# ETH_PCIE_PHY.net
KiCad netlist of a schematic drawn in Altium Designer
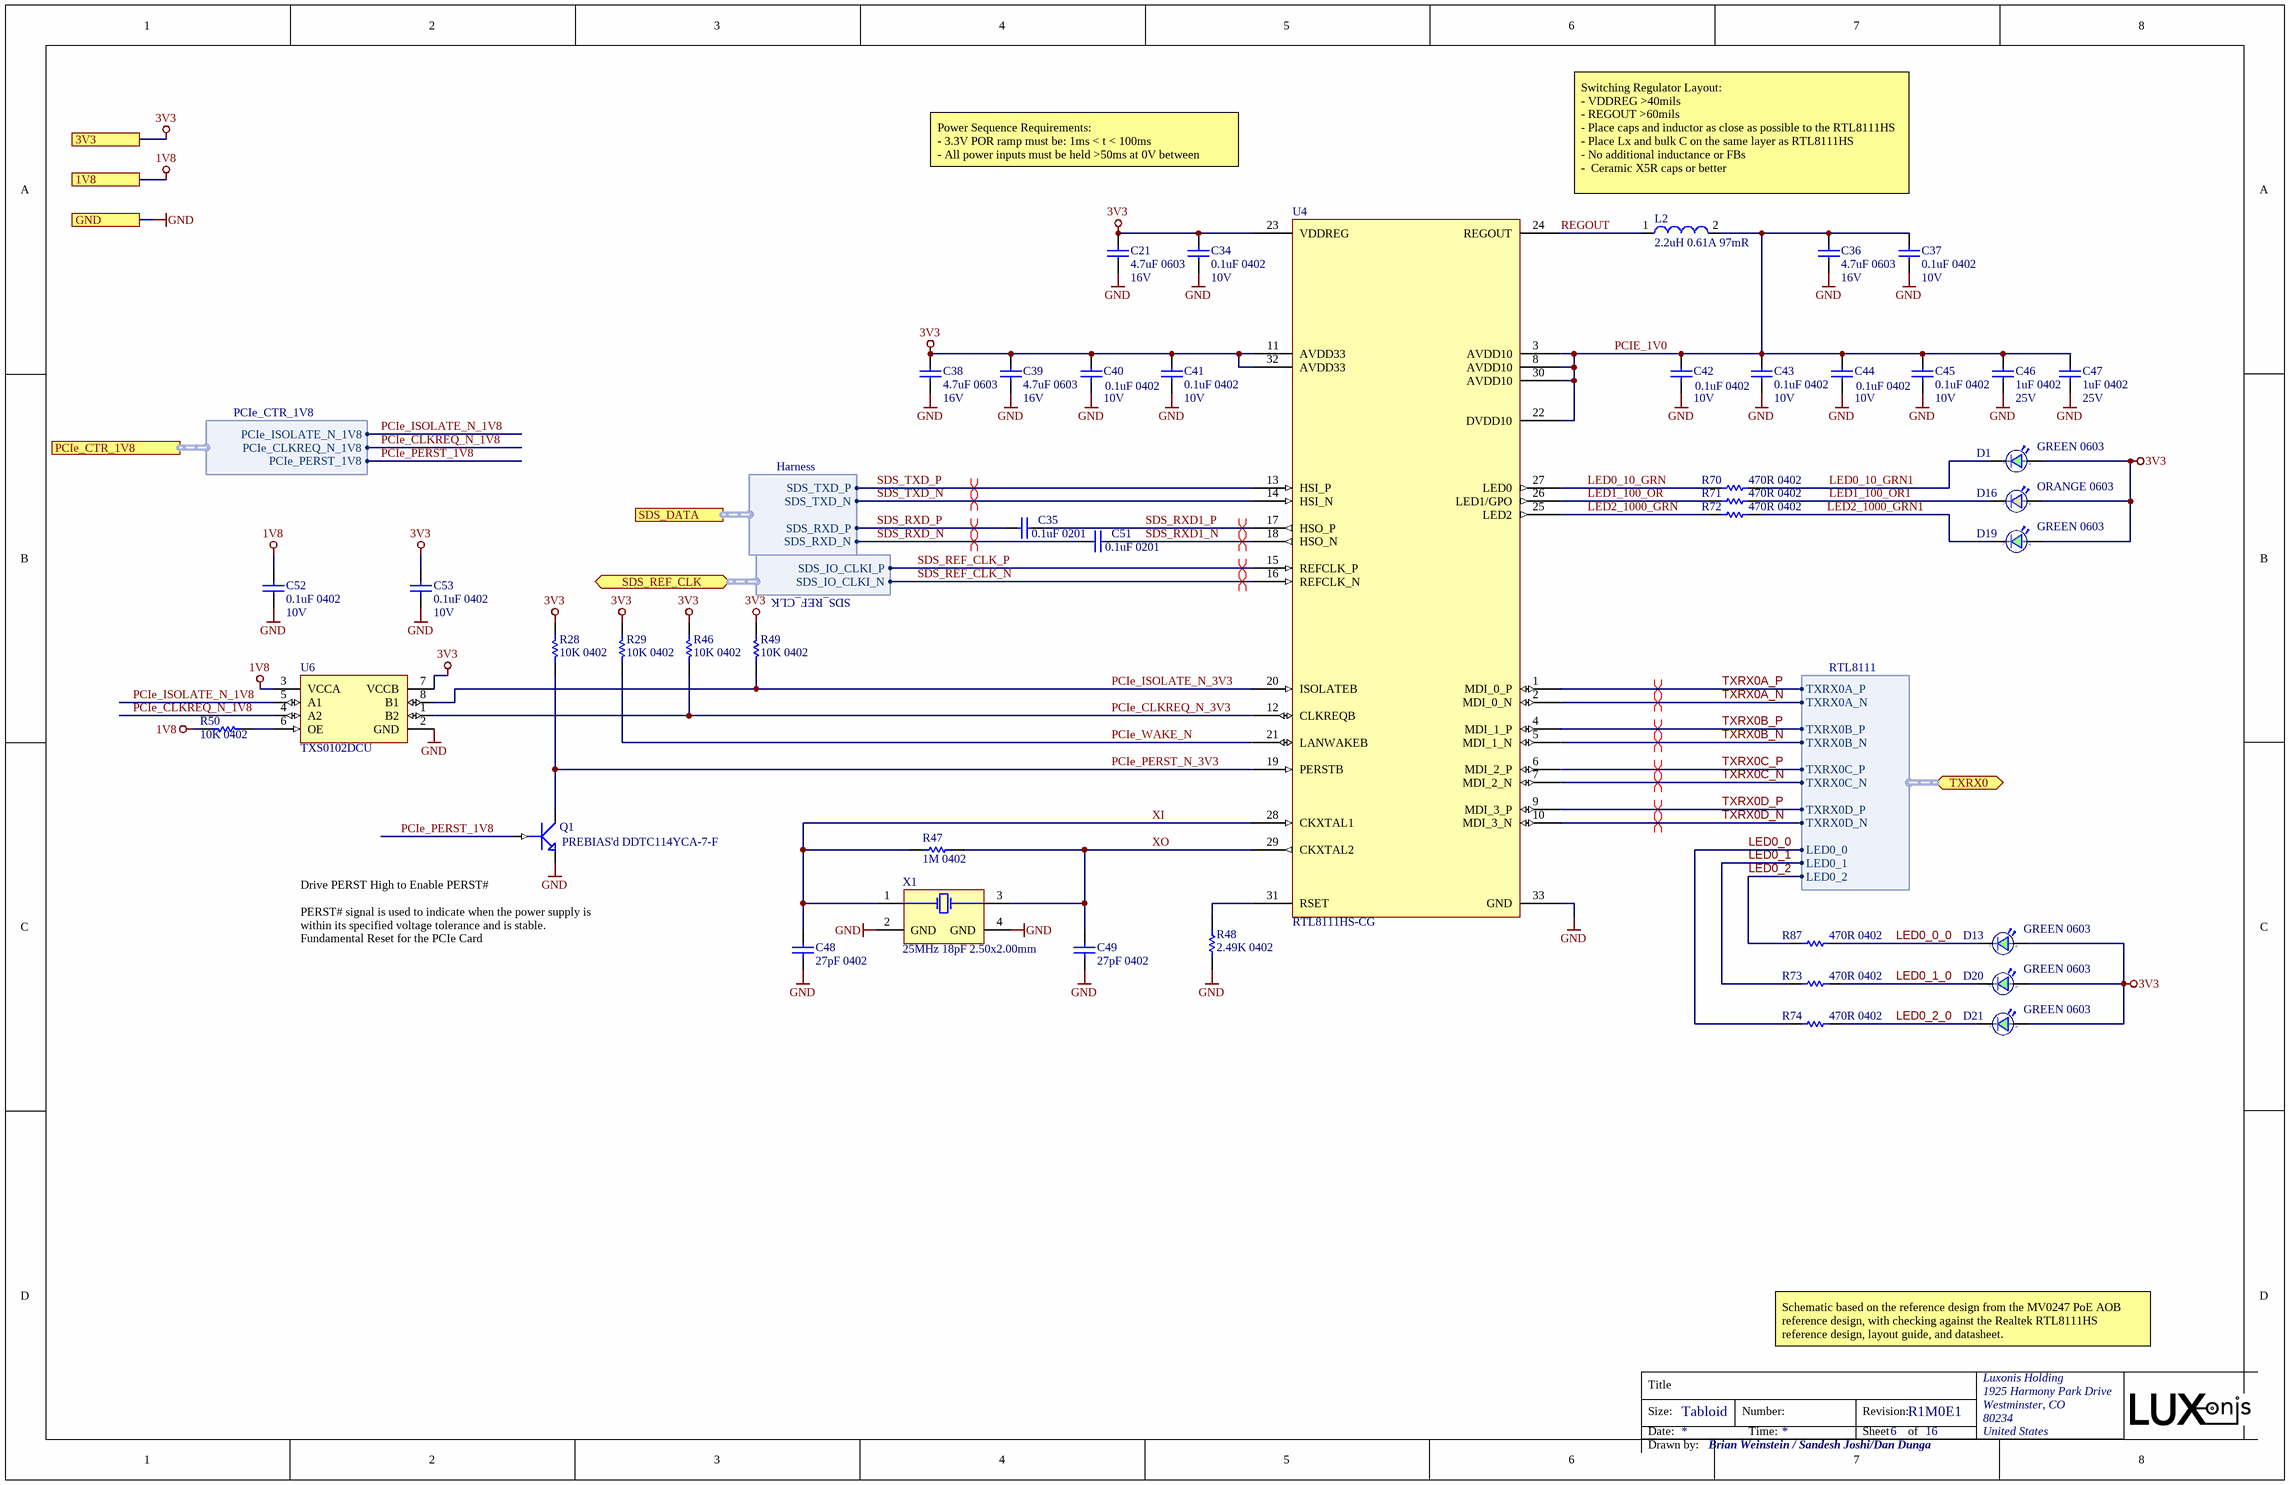
[diagram p0: ETH_PCIE_PHY.SchDoc]

(export (version "E")
  (design (tool "Eeschema 10.0.6"))
  (components
    (comp (ref "C21")
      (value "4.7uF 0603")
      (footprint "CAPC0603(1608)100_N")
      (description "CAP CER 4.7UF 16V X5R 0603 10%")
      (fields (field (name "TOLERANCE") "10%") (field (name "VOLTAGE RATING") "16V"))
      (libsource (lib "LuxonisMaster") (part "GRM188R61C475KAAJD"))
    )
    (comp (ref "C34")
      (value "0.1uF 0402")
      (footprint "CAP_Altium_Vault_Generic:CAPC0402(1005)70_N")
      (description "CAP CER 0.1UF 10V X7R 0402 5%")
      (fields (field (name "TOLERANCE") "5%") (field (name "VOLTAGE RATING") "10V"))
      (libsource (lib "LuxonisMaster") (part "GRM155R71A104JA01D"))
    )
    (comp (ref "C35")
      (value "0.1uF 0201")
      (footprint "CAP_Altium_Vault_Generic:CAPC0201(0603)33_L")
      (description "CAP CER 0.1UF 10V X5R 0201")
      (fields (field (name "TOLERANCE") "10%") (field (name "VOLTAGE") "10V"))
      (libsource (lib "LuxonisMaster") (part "GRM033R61A104KE15D"))
    )
    (comp (ref "C36")
      (value "4.7uF 0603")
      (footprint "CAPC0603(1608)100_N")
      (description "CAP CER 4.7UF 16V X5R 0603 10%")
      (fields (field (name "TOLERANCE") "10%") (field (name "VOLTAGE RATING") "16V"))
      (libsource (lib "LuxonisMaster") (part "GRM188R61C475KAAJD"))
    )
    (comp (ref "C37")
      (value "0.1uF 0402")
      (footprint "CAP_Altium_Vault_Generic:CAPC0402(1005)70_N")
      (description "CAP CER 0.1UF 10V X7R 0402 5%")
      (fields (field (name "TOLERANCE") "5%") (field (name "VOLTAGE RATING") "10V"))
      (libsource (lib "LuxonisMaster") (part "GRM155R71A104JA01D"))
    )
    (comp (ref "C38")
      (value "4.7uF 0603")
      (footprint "CAPC0603(1608)100_N")
      (description "CAP CER 4.7UF 16V X5R 0603 10%")
      (fields (field (name "TOLERANCE") "10%") (field (name "VOLTAGE RATING") "16V"))
      (libsource (lib "LuxonisMaster") (part "GRM188R61C475KAAJD"))
    )
    (comp (ref "C39")
      (value "4.7uF 0603")
      (footprint "CAPC0603(1608)100_N")
      (description "CAP CER 4.7UF 16V X5R 0603 10%")
      (fields (field (name "TOLERANCE") "10%") (field (name "VOLTAGE RATING") "16V"))
      (libsource (lib "LuxonisMaster") (part "GRM188R61C475KAAJD"))
    )
    (comp (ref "C40")
      (value "0.1uF 0402")
      (footprint "CAP_Altium_Vault_Generic:CAPC0402(1005)70_N")
      (description "CAP CER 0.1UF 10V X7R 0402 5%")
      (fields (field (name "TOLERANCE") "5%") (field (name "VOLTAGE RATING") "10V"))
      (libsource (lib "LuxonisMaster") (part "GRM155R71A104JA01D"))
    )
    (comp (ref "C41")
      (value "0.1uF 0402")
      (footprint "CAP_Altium_Vault_Generic:CAPC0402(1005)70_N")
      (description "CAP CER 0.1UF 10V X7R 0402 5%")
      (fields (field (name "TOLERANCE") "5%") (field (name "VOLTAGE RATING") "10V"))
      (libsource (lib "LuxonisMaster") (part "GRM155R71A104JA01D"))
    )
    (comp (ref "C42")
      (value "0.1uF 0402")
      (footprint "CAP_Altium_Vault_Generic:CAPC0402(1005)70_N")
      (description "CAP CER 0.1UF 10V X7R 0402 5%")
      (fields (field (name "TOLERANCE") "5%") (field (name "VOLTAGE RATING") "10V"))
      (libsource (lib "LuxonisMaster") (part "GRM155R71A104JA01D"))
    )
    (comp (ref "C43")
      (value "0.1uF 0402")
      (footprint "CAP_Altium_Vault_Generic:CAPC0402(1005)70_N")
      (description "CAP CER 0.1UF 10V X7R 0402 5%")
      (fields (field (name "TOLERANCE") "5%") (field (name "VOLTAGE RATING") "10V"))
      (libsource (lib "LuxonisMaster") (part "GRM155R71A104JA01D"))
    )
    (comp (ref "C44")
      (value "0.1uF 0402")
      (footprint "CAP_Altium_Vault_Generic:CAPC0402(1005)70_N")
      (description "CAP CER 0.1UF 10V X7R 0402 5%")
      (fields (field (name "TOLERANCE") "5%") (field (name "VOLTAGE RATING") "10V"))
      (libsource (lib "LuxonisMaster") (part "GRM155R71A104JA01D"))
    )
    (comp (ref "C45")
      (value "0.1uF 0402")
      (footprint "CAP_Altium_Vault_Generic:CAPC0402(1005)70_N")
      (description "CAP CER 0.1UF 10V X7R 0402 5%")
      (fields (field (name "TOLERANCE") "5%") (field (name "VOLTAGE RATING") "10V"))
      (libsource (lib "LuxonisMaster") (part "GRM155R71A104JA01D"))
    )
    (comp (ref "C46")
      (value "1uF 0402")
      (footprint "CAP_Altium_Vault_Generic:CAPC0402(1005)70_N")
      (description "CAP CER 1UF 25V X5R 0402 10%")
      (fields
        (field (name "TOLERANCE") "10%")
        (field (name "VOLTAGE") "25V")
        (field (name "VOLTAGE RATING") "25V")
      )
      (libsource (lib "LuxonisMaster") (part "GRM155R61E105KA12D"))
    )
    (comp (ref "C47")
      (value "1uF 0402")
      (footprint "CAP_Altium_Vault_Generic:CAPC0402(1005)70_N")
      (description "CAP CER 1UF 25V X5R 0402 10%")
      (fields
        (field (name "TOLERANCE") "10%")
        (field (name "VOLTAGE") "25V")
        (field (name "VOLTAGE RATING") "25V")
      )
      (libsource (lib "LuxonisMaster") (part "GRM155R61E105KA12D"))
    )
    (comp (ref "C48")
      (value "27pF 0402")
      (footprint "CAP_Altium_Vault_Generic:CAPC0402(1005)60_N")
      (description "CAP CER 27PF 50V C0G/NP0 0402")
      (fields (field (name "TOLERANCE") "5%") (field (name "VOLTAGE") "50V"))
      (libsource (lib "BW2098POE") (part "C0402C270J5GACTU"))
    )
    (comp (ref "C49")
      (value "27pF 0402")
      (footprint "CAP_Altium_Vault_Generic:CAPC0402(1005)60_N")
      (description "CAP CER 27PF 50V C0G/NP0 0402")
      (fields (field (name "TOLERANCE") "5%") (field (name "VOLTAGE") "50V"))
      (libsource (lib "BW2098POE") (part "C0402C270J5GACTU"))
    )
    (comp (ref "C51")
      (value "0.1uF 0201")
      (footprint "CAP_Altium_Vault_Generic:CAPC0201(0603)33_L")
      (description "CAP CER 0.1UF 10V X5R 0201")
      (fields (field (name "TOLERANCE") "10%") (field (name "VOLTAGE") "10V"))
      (libsource (lib "LuxonisMaster") (part "GRM033R61A104KE15D"))
    )
    (comp (ref "C52")
      (value "0.1uF 0402")
      (footprint "CAP_Altium_Vault_Generic:CAPC0402(1005)70_N")
      (description "CAP CER 0.1UF 10V X7R 0402 5%")
      (fields (field (name "TOLERANCE") "5%") (field (name "VOLTAGE RATING") "10V"))
      (libsource (lib "LuxonisMaster") (part "GRM155R71A104JA01D"))
    )
    (comp (ref "C53")
      (value "0.1uF 0402")
      (footprint "CAP_Altium_Vault_Generic:CAPC0402(1005)70_N")
      (description "CAP CER 0.1UF 10V X7R 0402 5%")
      (fields (field (name "TOLERANCE") "5%") (field (name "VOLTAGE RATING") "10V"))
      (libsource (lib "LuxonisMaster") (part "GRM155R71A104JA01D"))
    )
    (comp (ref "D1")
      (value "GREEN 0603")
      (footprint "SML_D1xx8W")
      (description "LED GREEN DIFFUSED 0603 SMD Green 572nm LED Indication - Discrete 2.2V 0603 (1608 Metric)")
      (fields (field (name "MANUFACTURER") "Rohm") (field (name "MANUFACTURER PART NUMBER") "SML-D12M8WT86"))
      (libsource (lib "LuxonisMaster") (part "SML-D12M8WT86"))
    )
    (comp (ref "D13")
      (value "GREEN 0603")
      (footprint "SML_D1xx8W")
      (description "LED GREEN DIFFUSED 0603 SMD Green 572nm LED Indication - Discrete 2.2V 0603 (1608 Metric)")
      (fields (field (name "MANUFACTURER") "Rohm") (field (name "MANUFACTURER PART NUMBER") "SML-D12M8WT86"))
      (libsource (lib "LuxonisMaster") (part "SML-D12M8WT86"))
    )
    (comp (ref "D16")
      (value "ORANGE 0603")
      (footprint "LuxonisMaster:SML_D1xx8W")
      (description "LED ORANGE DIFFUSED 0603 SMD Orange 605nm LED Indication - Discrete 2.2V 0603 (1608 Metric)")
      (libsource (lib "LuxonisMaster") (part "SML-D12D8WT86"))
    )
    (comp (ref "D19")
      (value "GREEN 0603")
      (footprint "SML_D1xx8W")
      (description "LED GREEN DIFFUSED 0603 SMD Green 572nm LED Indication - Discrete 2.2V 0603 (1608 Metric)")
      (fields (field (name "MANUFACTURER") "Rohm") (field (name "MANUFACTURER PART NUMBER") "SML-D12M8WT86"))
      (libsource (lib "LuxonisMaster") (part "SML-D12M8WT86"))
    )
    (comp (ref "D20")
      (value "GREEN 0603")
      (footprint "SML_D1xx8W")
      (description "LED GREEN DIFFUSED 0603 SMD Green 572nm LED Indication - Discrete 2.2V 0603 (1608 Metric)")
      (fields (field (name "MANUFACTURER") "Rohm") (field (name "MANUFACTURER PART NUMBER") "SML-D12M8WT86"))
      (libsource (lib "LuxonisMaster") (part "SML-D12M8WT86"))
    )
    (comp (ref "D21")
      (value "GREEN 0603")
      (footprint "SML_D1xx8W")
      (description "LED GREEN DIFFUSED 0603 SMD Green 572nm LED Indication - Discrete 2.2V 0603 (1608 Metric)")
      (fields (field (name "MANUFACTURER") "Rohm") (field (name "MANUFACTURER PART NUMBER") "SML-D12M8WT86"))
      (libsource (lib "LuxonisMaster") (part "SML-D12M8WT86"))
    )
    (comp (ref "L2")
      (value "2.2uH 0.61A 97mR")
      (footprint "BW2098POE:LQH32NH2R2J23L")
      (description "FIXED IND 2.2UH 610MA 97MOHM SMD")
      (fields (field (name "TOLERANCE") "5%"))
      (libsource (lib "BW2098POE") (part "LQH32NH2R2J23L"))
    )
    (comp (ref "Q1")
      (value "PREBIAS'd DDTC114YCA-7-F")
      (footprint "BW2098POE:DDTC114YCA-7-F")
      (description "TRANS PREBIAS NPN 200MW SOT23-3")
      (libsource (lib "BW2098POE") (part "DDTC114YCA-7-F"))
    )
    (comp (ref "R28")
      (value "10K 0402")
      (footprint "RESC0402(1005)_N")
      (fields (field (name "TOLERANCE") "1%"))
      (libsource (lib "LuxonisMaster") (part "RC0402FR-1310KL"))
    )
    (comp (ref "R29")
      (value "10K 0402")
      (footprint "RESC0402(1005)_N")
      (fields (field (name "TOLERANCE") "1%"))
      (libsource (lib "LuxonisMaster") (part "RC0402FR-1310KL"))
    )
    (comp (ref "R46")
      (value "10K 0402")
      (footprint "RESC0402(1005)_N")
      (fields (field (name "TOLERANCE") "1%"))
      (libsource (lib "LuxonisMaster") (part "RC0402FR-1310KL"))
    )
    (comp (ref "R47")
      (value "1M 0402")
      (footprint "RESC0402(1005)_N")
      (description "RES SMD 1M OHM 1% 1/16W 0402")
      (fields (field (name "TOLERANCE") "1%"))
      (libsource (lib "LuxonisMaster") (part "RC0402FR-071ML"))
    )
    (comp (ref "R48")
      (value "2.49K 0402")
      (footprint "RESC0402(1005)_N")
      (description "RES SMD 2.49K OHM 1% 1/16W 0402")
      (fields (field (name "TOLERANCE") "1%"))
      (libsource (lib "BW2098POE") (part "RC0402FR-072K49L"))
    )
    (comp (ref "R49")
      (value "10K 0402")
      (footprint "RESC0402(1005)_N")
      (fields (field (name "TOLERANCE") "1%"))
      (libsource (lib "LuxonisMaster") (part "RC0402FR-1310KL"))
    )
    (comp (ref "R50")
      (value "10K 0402")
      (footprint "RESC0402(1005)_N")
      (fields (field (name "TOLERANCE") "1%"))
      (libsource (lib "LuxonisMaster") (part "RC0402FR-1310KL"))
    )
    (comp (ref "R70")
      (value "470R 0402")
      (footprint "RESC0402(1005)_N")
      (description "RES SMD 470 OHM 1% 1/16W 0402")
      (fields (field (name "TOLERANCE") "1%"))
      (libsource (lib "LuxonisMaster") (part "CRCW0402470RFKED"))
    )
    (comp (ref "R71")
      (value "470R 0402")
      (footprint "RESC0402(1005)_N")
      (description "RES SMD 470 OHM 1% 1/16W 0402")
      (fields (field (name "TOLERANCE") "1%"))
      (libsource (lib "LuxonisMaster") (part "CRCW0402470RFKED"))
    )
    (comp (ref "R72")
      (value "470R 0402")
      (footprint "RESC0402(1005)_N")
      (description "RES SMD 470 OHM 1% 1/16W 0402")
      (fields (field (name "TOLERANCE") "1%"))
      (libsource (lib "LuxonisMaster") (part "CRCW0402470RFKED"))
    )
    (comp (ref "R73")
      (value "470R 0402")
      (footprint "RESC0402(1005)_N")
      (description "RES SMD 470 OHM 1% 1/16W 0402")
      (fields (field (name "TOLERANCE") "1%"))
      (libsource (lib "LuxonisMaster") (part "CRCW0402470RFKED"))
    )
    (comp (ref "R74")
      (value "470R 0402")
      (footprint "RESC0402(1005)_N")
      (description "RES SMD 470 OHM 1% 1/16W 0402")
      (fields (field (name "TOLERANCE") "1%"))
      (libsource (lib "LuxonisMaster") (part "CRCW0402470RFKED"))
    )
    (comp (ref "R87")
      (value "470R 0402")
      (footprint "RESC0402(1005)_N")
      (description "RES SMD 470 OHM 1% 1/16W 0402")
      (fields (field (name "TOLERANCE") "1%"))
      (libsource (lib "LuxonisMaster") (part "CRCW0402470RFKED"))
    )
    (comp (ref "U4")
      (value "RTL8111HS-CG")
      (footprint "BW2098POE:RTL8111Hx-CG")
      (description "IC ETHERNET/PCIe PHY Realtek")
      (libsource (lib "BW2098POE") (part "RTL8111HS"))
    )
    (comp (ref "U6")
      (value "TXS0102DCU")
      (footprint "BW2098POE:TXS0102DCUR")
      (description "TEXAS INSTRUMENTS - TXS0102DCUR - IC, TRANSLATOR, 2 BIT, BI, US-8")
      (libsource (lib "BW2098POE") (part "TXS0102DCUR"))
    )
    (comp (ref "X1")
      (value "25MHz 18pF 2.50x2.00mm")
      (footprint "BW2098POE:ECS-250-18-36B-CKY-TR")
      (description "CRYSTAL 25.0000MHZ 18PF SMD 25MHz ±10ppm Crystal 18pF 50 Ohms 4-SMD, No Lead")
      (libsource (lib "BW2098POE") (part "ECS-250-18-36B-CKY-TR"))
    )
  )
  (nets
    (net (code "5") (name "/LED0_0") (class "Default")
      (node (ref "R74") (pin "1") (pinfunction "1_1") (pintype "passive"))
    )
    (net (code "6") (name "/LED0_0_0") (class "Default")
      (node (ref "D13") (pin "1") (pinfunction "C_1") (pintype "passive"))
      (node (ref "R87") (pin "2") (pinfunction "2_2") (pintype "passive"))
    )
    (net (code "7") (name "/LED0_1") (class "Default")
      (node (ref "R73") (pin "1") (pinfunction "1_1") (pintype "passive"))
    )
    (net (code "8") (name "/LED0_1_0") (class "Default")
      (node (ref "D20") (pin "1") (pinfunction "C_1") (pintype "passive"))
      (node (ref "R73") (pin "2") (pinfunction "2_2") (pintype "passive"))
    )
    (net (code "9") (name "/LED0_2") (class "Default")
      (node (ref "R87") (pin "1") (pinfunction "1_1") (pintype "passive"))
    )
    (net (code "10") (name "/LED0_2_0") (class "Default")
      (node (ref "D21") (pin "1") (pinfunction "C_1") (pintype "passive"))
      (node (ref "R74") (pin "2") (pinfunction "2_2") (pintype "passive"))
    )
    (net (code "11") (name "/LED0_10_GRN") (class "Default")
      (node (ref "R70") (pin "1") (pinfunction "1_1") (pintype "passive"))
      (node (ref "U4") (pin "27") (pinfunction "LED0_27") (pintype "output"))
    )
    (net (code "12") (name "/LED0_10_GRN1") (class "Default")
      (node (ref "D1") (pin "1") (pinfunction "C_1") (pintype "passive"))
      (node (ref "R70") (pin "2") (pinfunction "2_2") (pintype "passive"))
    )
    (net (code "13") (name "/LED1_100_OR") (class "Default")
      (node (ref "R71") (pin "1") (pinfunction "1_1") (pintype "passive"))
      (node (ref "U4") (pin "26") (pinfunction "LED1/GPO_26") (pintype "output"))
    )
    (net (code "14") (name "/LED1_100_OR1") (class "Default")
      (node (ref "D16") (pin "1") (pinfunction "C_1") (pintype "passive"))
      (node (ref "R71") (pin "2") (pinfunction "2_2") (pintype "passive"))
    )
    (net (code "15") (name "/LED2_1000_GRN") (class "Default")
      (node (ref "R72") (pin "1") (pinfunction "1_1") (pintype "passive"))
      (node (ref "U4") (pin "25") (pinfunction "LED2_25") (pintype "output"))
    )
    (net (code "16") (name "/LED2_1000_GRN1") (class "Default")
      (node (ref "D19") (pin "1") (pinfunction "C_1") (pintype "passive"))
      (node (ref "R72") (pin "2") (pinfunction "2_2") (pintype "passive"))
    )
    (net (code "17") (name "/PCIE_1V0") (class "Default")
      (node (ref "C36") (pin "2") (pinfunction "2_2") (pintype "passive"))
      (node (ref "C37") (pin "2") (pinfunction "2_2") (pintype "passive"))
      (node (ref "C42") (pin "2") (pinfunction "2_2") (pintype "passive"))
      (node (ref "C43") (pin "2") (pinfunction "2_2") (pintype "passive"))
      (node (ref "C44") (pin "2") (pinfunction "2_2") (pintype "passive"))
      (node (ref "C45") (pin "2") (pinfunction "2_2") (pintype "passive"))
      (node (ref "C46") (pin "2") (pinfunction "2_2") (pintype "passive"))
      (node (ref "C47") (pin "2") (pinfunction "2_2") (pintype "passive"))
      (node (ref "L2") (pin "2") (pinfunction "2_2") (pintype "passive"))
      (node (ref "U4") (pin "22") (pinfunction "DVDD10_22") (pintype "passive"))
      (node (ref "U4") (pin "3") (pinfunction "AVDD10_3") (pintype "passive"))
      (node (ref "U4") (pin "30") (pinfunction "AVDD10_30") (pintype "passive"))
      (node (ref "U4") (pin "8") (pinfunction "AVDD10_8") (pintype "passive"))
    )
    (net (code "18") (name "/PCIe_CLKREQ_N_1V8") (class "Default")
      (node (ref "U6") (pin "4") (pinfunction "A2_4") (pintype "bidirectional"))
    )
    (net (code "19") (name "/PCIe_CLKREQ_N_3V3") (class "Default")
      (node (ref "R46") (pin "2") (pinfunction "2_2") (pintype "passive"))
      (node (ref "U4") (pin "12") (pinfunction "CLKREQB_12") (pintype "bidirectional"))
      (node (ref "U6") (pin "1") (pinfunction "B2_1") (pintype "bidirectional"))
    )
    (net (code "20") (name "/PCIe_ISOLATE_N_1V8") (class "Default")
      (node (ref "U6") (pin "5") (pinfunction "A1_5") (pintype "bidirectional"))
    )
    (net (code "21") (name "/PCIe_ISOLATE_N_3V3") (class "Default")
      (node (ref "R49") (pin "2") (pinfunction "2_2") (pintype "passive"))
      (node (ref "U4") (pin "20") (pinfunction "ISOLATEB_20") (pintype "input"))
      (node (ref "U6") (pin "8") (pinfunction "B1_8") (pintype "bidirectional"))
    )
    (net (code "22") (name "/PCIe_PERST_1V8") (class "Default")
      (node (ref "Q1") (pin "1") (pinfunction "B_1") (pintype "input"))
    )
    (net (code "23") (name "/PCIe_PERST_N_3V3") (class "Default")
      (node (ref "Q1") (pin "3") (pinfunction "C_3") (pintype "passive"))
      (node (ref "R28") (pin "2") (pinfunction "2_2") (pintype "passive"))
      (node (ref "U4") (pin "19") (pinfunction "PERSTB_19") (pintype "input"))
    )
    (net (code "24") (name "/PCIe_WAKE_N") (class "Default")
      (node (ref "R29") (pin "2") (pinfunction "2_2") (pintype "passive"))
      (node (ref "U4") (pin "21") (pinfunction "LANWAKEB_21") (pintype "bidirectional"))
    )
    (net (code "25") (name "/REGOUT") (class "Default")
      (node (ref "L2") (pin "1") (pinfunction "1_1") (pintype "passive"))
      (node (ref "U4") (pin "24") (pinfunction "REGOUT_24") (pintype "passive"))
    )
    (net (code "26") (name "/SDS_REF_CLK_N") (class "Default")
      (node (ref "U4") (pin "16") (pinfunction "REFCLK_N_16") (pintype "input"))
    )
    (net (code "27") (name "/SDS_REF_CLK_P") (class "Default")
      (node (ref "U4") (pin "15") (pinfunction "REFCLK_P_15") (pintype "input"))
    )
    (net (code "28") (name "/SDS_RXD1_N") (class "Default")
      (node (ref "C51") (pin "2") (pinfunction "2_2") (pintype "passive"))
      (node (ref "U4") (pin "18") (pinfunction "HSO_N_18") (pintype "output"))
    )
    (net (code "29") (name "/SDS_RXD1_P") (class "Default")
      (node (ref "C35") (pin "2") (pinfunction "2_2") (pintype "passive"))
      (node (ref "U4") (pin "17") (pinfunction "HSO_P_17") (pintype "output"))
    )
    (net (code "30") (name "/SDS_RXD_N") (class "Default")
      (node (ref "C51") (pin "1") (pinfunction "1_1") (pintype "passive"))
    )
    (net (code "31") (name "/SDS_RXD_P") (class "Default")
      (node (ref "C35") (pin "1") (pinfunction "1_1") (pintype "passive"))
    )
    (net (code "32") (name "/SDS_TXD_N") (class "Default")
      (node (ref "U4") (pin "14") (pinfunction "HSI_N_14") (pintype "input"))
    )
    (net (code "33") (name "/SDS_TXD_P") (class "Default")
      (node (ref "U4") (pin "13") (pinfunction "HSI_P_13") (pintype "input"))
    )
    (net (code "34") (name "/TXRX0A_N") (class "Default")
      (node (ref "U4") (pin "2") (pinfunction "MDI_0_N_2") (pintype "bidirectional"))
    )
    (net (code "35") (name "/TXRX0A_P") (class "Default")
      (node (ref "U4") (pin "1") (pinfunction "MDI_0_P_1") (pintype "bidirectional"))
    )
    (net (code "36") (name "/TXRX0B_N") (class "Default")
      (node (ref "U4") (pin "5") (pinfunction "MDI_1_N_5") (pintype "bidirectional"))
    )
    (net (code "37") (name "/TXRX0B_P") (class "Default")
      (node (ref "U4") (pin "4") (pinfunction "MDI_1_P_4") (pintype "bidirectional"))
    )
    (net (code "38") (name "/TXRX0C_N") (class "Default")
      (node (ref "U4") (pin "7") (pinfunction "MDI_2_N_7") (pintype "bidirectional"))
    )
    (net (code "39") (name "/TXRX0C_P") (class "Default")
      (node (ref "U4") (pin "6") (pinfunction "MDI_2_P_6") (pintype "bidirectional"))
    )
    (net (code "40") (name "/TXRX0D_N") (class "Default")
      (node (ref "U4") (pin "10") (pinfunction "MDI_3_N_10") (pintype "bidirectional"))
    )
    (net (code "41") (name "/TXRX0D_P") (class "Default")
      (node (ref "U4") (pin "9") (pinfunction "MDI_3_P_9") (pintype "bidirectional"))
    )
    (net (code "42") (name "/XI") (class "Default")
      (node (ref "C48") (pin "2") (pinfunction "2_2") (pintype "passive"))
      (node (ref "R47") (pin "1") (pinfunction "1_1") (pintype "passive"))
      (node (ref "U4") (pin "28") (pinfunction "CKXTAL1_28") (pintype "input"))
      (node (ref "X1") (pin "1") (pinfunction "X1_1") (pintype "passive"))
    )
    (net (code "43") (name "/XO") (class "Default")
      (node (ref "C49") (pin "2") (pinfunction "2_2") (pintype "passive"))
      (node (ref "R47") (pin "2") (pinfunction "2_2") (pintype "passive"))
      (node (ref "U4") (pin "29") (pinfunction "CKXTAL2_29") (pintype "output"))
      (node (ref "X1") (pin "3") (pinfunction "X2_3") (pintype "passive"))
    )
    (net (code "48") (name "1V8") (class "Default")
      (node (ref "C52") (pin "2") (pinfunction "2_2") (pintype "passive"))
      (node (ref "R50") (pin "2") (pinfunction "2_2") (pintype "passive"))
      (node (ref "U6") (pin "3") (pinfunction "VCCA_3") (pintype "power_in"))
    )
    (net (code "49") (name "3V3") (class "Default")
      (node (ref "C21") (pin "2") (pinfunction "2_2") (pintype "passive"))
      (node (ref "C34") (pin "2") (pinfunction "2_2") (pintype "passive"))
      (node (ref "C38") (pin "2") (pinfunction "2_2") (pintype "passive"))
      (node (ref "C39") (pin "2") (pinfunction "2_2") (pintype "passive"))
      (node (ref "C40") (pin "2") (pinfunction "2_2") (pintype "passive"))
      (node (ref "C41") (pin "2") (pinfunction "2_2") (pintype "passive"))
      (node (ref "C53") (pin "2") (pinfunction "2_2") (pintype "passive"))
      (node (ref "D1") (pin "2") (pinfunction "A_2") (pintype "passive"))
      (node (ref "D13") (pin "2") (pinfunction "A_2") (pintype "passive"))
      (node (ref "D16") (pin "2") (pinfunction "A_2") (pintype "passive"))
      (node (ref "D19") (pin "2") (pinfunction "A_2") (pintype "passive"))
      (node (ref "D20") (pin "2") (pinfunction "A_2") (pintype "passive"))
      (node (ref "D21") (pin "2") (pinfunction "A_2") (pintype "passive"))
      (node (ref "R28") (pin "1") (pinfunction "1_1") (pintype "passive"))
      (node (ref "R29") (pin "1") (pinfunction "1_1") (pintype "passive"))
      (node (ref "R46") (pin "1") (pinfunction "1_1") (pintype "passive"))
      (node (ref "R49") (pin "1") (pinfunction "1_1") (pintype "passive"))
      (node (ref "U4") (pin "11") (pinfunction "AVDD33_11") (pintype "passive"))
      (node (ref "U4") (pin "23") (pinfunction "VDDREG_23") (pintype "passive"))
      (node (ref "U4") (pin "32") (pinfunction "AVDD33_32") (pintype "passive"))
      (node (ref "U6") (pin "7") (pinfunction "VCCB_7") (pintype "power_in"))
    )
    (net (code "50") (name "GND") (class "Default")
      (node (ref "C21") (pin "1") (pinfunction "1_1") (pintype "passive"))
      (node (ref "C34") (pin "1") (pinfunction "1_1") (pintype "passive"))
      (node (ref "C36") (pin "1") (pinfunction "1_1") (pintype "passive"))
      (node (ref "C37") (pin "1") (pinfunction "1_1") (pintype "passive"))
      (node (ref "C38") (pin "1") (pinfunction "1_1") (pintype "passive"))
      (node (ref "C39") (pin "1") (pinfunction "1_1") (pintype "passive"))
      (node (ref "C40") (pin "1") (pinfunction "1_1") (pintype "passive"))
      (node (ref "C41") (pin "1") (pinfunction "1_1") (pintype "passive"))
      (node (ref "C42") (pin "1") (pinfunction "1_1") (pintype "passive"))
      (node (ref "C43") (pin "1") (pinfunction "1_1") (pintype "passive"))
      (node (ref "C44") (pin "1") (pinfunction "1_1") (pintype "passive"))
      (node (ref "C45") (pin "1") (pinfunction "1_1") (pintype "passive"))
      (node (ref "C46") (pin "1") (pinfunction "1_1") (pintype "passive"))
      (node (ref "C47") (pin "1") (pinfunction "1_1") (pintype "passive"))
      (node (ref "C48") (pin "1") (pinfunction "1_1") (pintype "passive"))
      (node (ref "C49") (pin "1") (pinfunction "1_1") (pintype "passive"))
      (node (ref "C52") (pin "1") (pinfunction "1_1") (pintype "passive"))
      (node (ref "C53") (pin "1") (pinfunction "1_1") (pintype "passive"))
      (node (ref "Q1") (pin "2") (pinfunction "E_2") (pintype "passive"))
      (node (ref "R48") (pin "1") (pinfunction "1_1") (pintype "passive"))
      (node (ref "U4") (pin "33") (pinfunction "GND_33") (pintype "passive"))
      (node (ref "U6") (pin "2") (pinfunction "GND_2") (pintype "power_in"))
      (node (ref "X1") (pin "2") (pinfunction "GND_2") (pintype "power_in"))
      (node (ref "X1") (pin "4") (pinfunction "GND_4") (pintype "power_in"))
    )
    (net (code "51") (name "Net-(U4-RSET)") (class "Default")
      (node (ref "R48") (pin "2") (pinfunction "2_2") (pintype "passive"))
      (node (ref "U4") (pin "31") (pinfunction "RSET_31") (pintype "passive"))
    )
    (net (code "52") (name "Net-(U6-OE)") (class "Default")
      (node (ref "R50") (pin "1") (pinfunction "1_1") (pintype "passive"))
      (node (ref "U6") (pin "6") (pinfunction "OE_6") (pintype "input"))
    )
  )
)
